# Trepanat_Output.net
KiCad netlist of a schematic drawn in Altium Designer
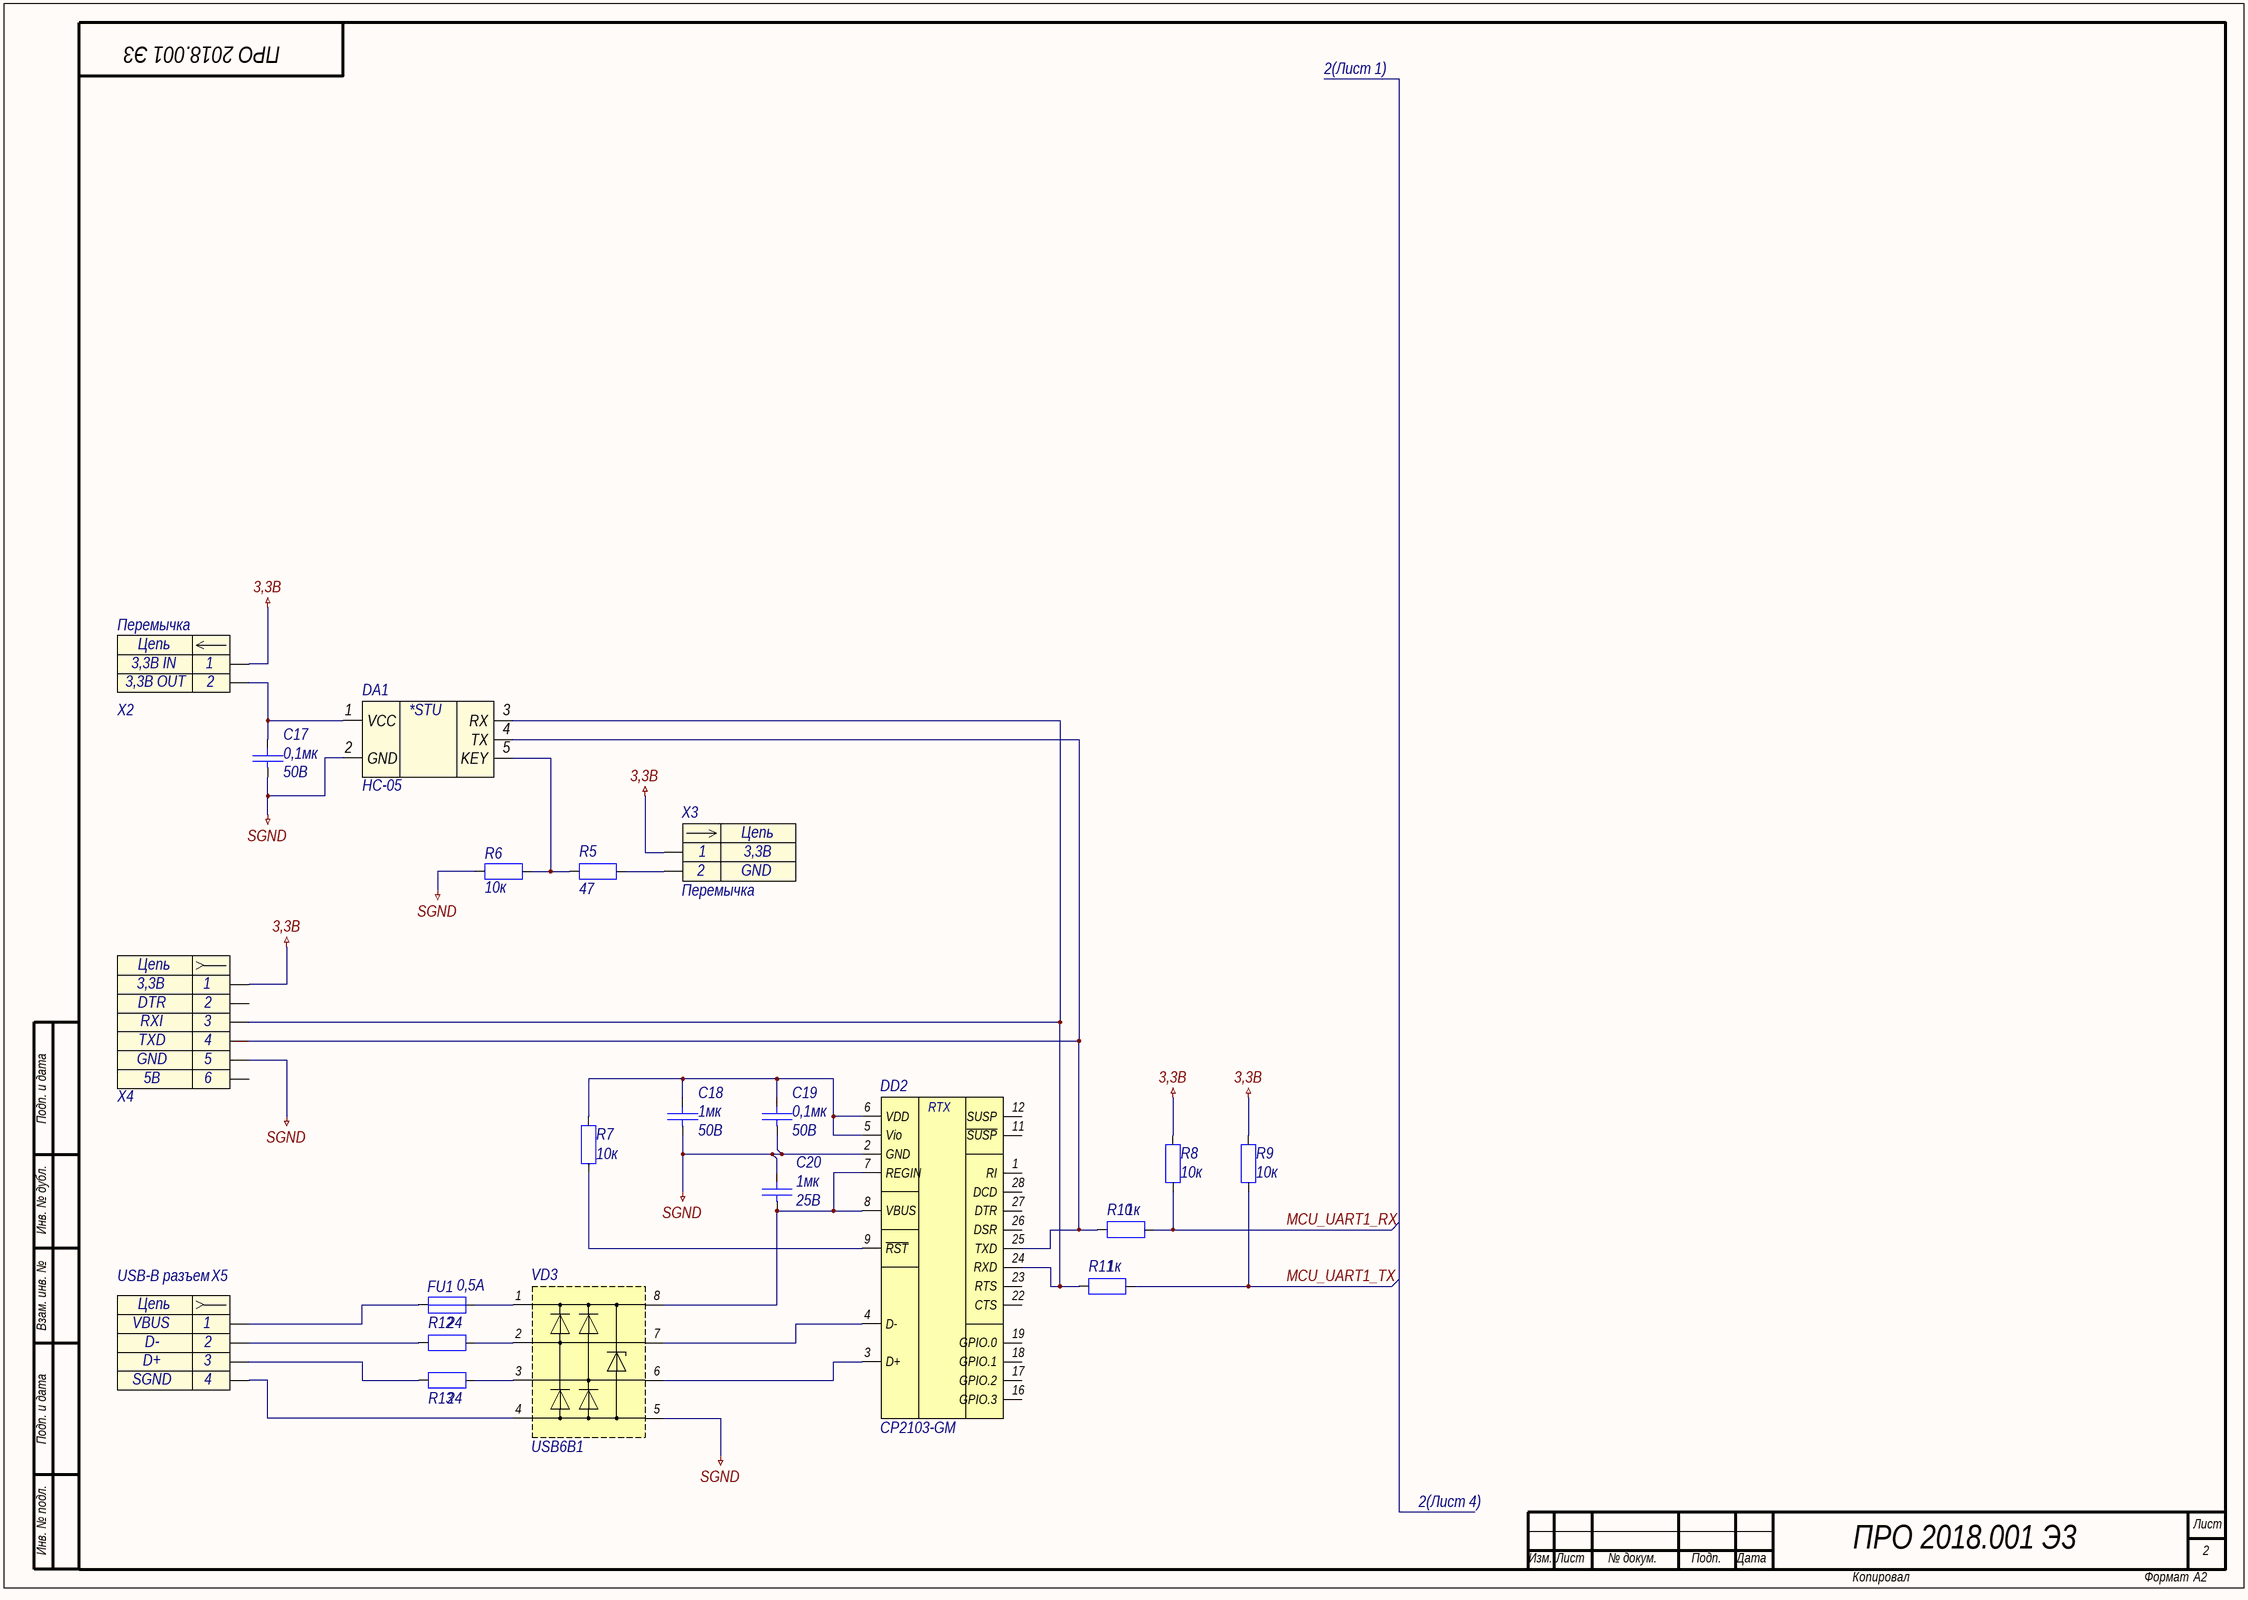
[diagram p0: Trepanat_Output.SchDoc]

(export (version "E")
  (design (tool "Eeschema 10.0.6"))
  (components
    (comp (ref "C17")
      (value "0,1мк")
      (footprint "ZabugorLib:C0805")
      (description "Конденсатор")
      (fields (field (name "VOLTAGE") "50В"))
      (libsource (lib "ZabugorLib") (part "Capacitor"))
    )
    (comp (ref "C18")
      (value "1мк")
      (footprint "ZabugorLib:C0805")
      (description "Конденсатор")
      (fields (field (name "VOLTAGE") "50В"))
      (libsource (lib "ZabugorLib") (part "Capacitor"))
    )
    (comp (ref "C19")
      (value "0,1мк")
      (footprint "ZabugorLib:C0805")
      (description "Конденсатор")
      (fields (field (name "VOLTAGE") "50В"))
      (libsource (lib "ZabugorLib") (part "Capacitor"))
    )
    (comp (ref "C20")
      (value "1мк")
      (footprint "ZabugorLib:C0805")
      (description "Конденсатор")
      (fields (field (name "VOLTAGE") "25В"))
      (libsource (lib "ZabugorLib") (part "Capacitor"))
    )
    (comp (ref "DA1")
      (value "HC-05")
      (footprint "HC-05")
      (description "Bluetooth HC-05")
      (libsource (lib "ZabugorLib") (part "HC-05"))
    )
    (comp (ref "DD2")
      (value "CP2103-GM")
      (footprint "ZabugorLib:QFN28")
      (description "USB-UART преобразователь")
      (fields (field (name "NAME") "CP2103-GM"))
      (libsource (lib "ZabugorLib") (part "CP2103"))
    )
    (comp (ref "FU1")
      (value "0,5A")
      (footprint "ZabugorLib:R1812")
      (description "Предохранитель")
      (fields (field (name "Comment") "MF-MSMF050"))
      (libsource (lib "ZabugorLib") (part "Fuse"))
    )
    (comp (ref "R5")
      (value "47")
      (footprint "ZabugorLib:R0805")
      (description "Резистор")
      (libsource (lib "") (part "Resistor_2"))
    )
    (comp (ref "R6")
      (value "10к")
      (footprint "ZabugorLib:R0805")
      (description "Резистор")
      (libsource (lib "") (part "Resistor_1"))
    )
    (comp (ref "R7")
      (value "10к")
      (footprint "ZabugorLib:R0805")
      (description "Резистор")
      (libsource (lib "ZabugorLib") (part "Resistor"))
    )
    (comp (ref "R8")
      (value "10к")
      (footprint "ZabugorLib:R0805")
      (description "Резистор")
      (libsource (lib "ZabugorLib") (part "Resistor"))
    )
    (comp (ref "R9")
      (value "10к")
      (footprint "ZabugorLib:R0805")
      (description "Резистор")
      (libsource (lib "ZabugorLib") (part "Resistor"))
    )
    (comp (ref "R10")
      (value "1к")
      (footprint "ZabugorLib:R0805")
      (description "Резистор")
      (libsource (lib "") (part "Resistor_2"))
    )
    (comp (ref "R11")
      (value "1к")
      (footprint "ZabugorLib:R0805")
      (description "Резистор")
      (libsource (lib "") (part "Resistor_2"))
    )
    (comp (ref "R12")
      (value "24")
      (footprint "ZabugorLib:R0805")
      (description "Резистор")
      (libsource (lib "") (part "Resistor_1"))
    )
    (comp (ref "R13")
      (value "24")
      (footprint "ZabugorLib:R0805")
      (description "Резистор")
      (libsource (lib "") (part "Resistor_1"))
    )
    (comp (ref "VD3")
      (value "USB6B1")
      (footprint "ZabugorLib:SO8")
      (description "Защита линии данных")
      (fields (field (name "NAME") "USB6B1"))
      (libsource (lib "ZabugorLib") (part "USB6B1"))
    )
    (comp (ref "X2")
      (value "Перемычка")
      (footprint "ZabugorLib:PLS2-2")
      (description "Разъем - 2 конт. вилка")
      (fields (field (name "NAME") "Перемычка"))
      (libsource (lib "ZabugorLib") (part "Header_2_plg"))
    )
    (comp (ref "X3")
      (value "Перемычка")
      (footprint "ZabugorLib:PLS2-2")
      (description "Разъем - 2 конт. вилка")
      (fields (field (name "NAME") "Перемычка"))
      (libsource (lib "") (part "Header_2_plg_1"))
    )
    (comp (ref "X4")
      (value "~")
      (footprint "ZabugorLib:PLS-6")
      (description "Разъем - 5 конт. розетка")
      (libsource (lib "ZabugorLib") (part "Header_6_sct"))
    )
    (comp (ref "X5")
      (value "670687041")
      (footprint "ZabugorLib:USBB-J1")
      (description "Разъем - 4 конт. розетка")
      (libsource (lib "ZabugorLib") (part "Header_4_sct"))
    )
  )
  (nets
    (net (code "1") (name "/MCU_UART1_RX") (class "Default")
      (node (ref "R10") (pin "1") (pinfunction "1_1") (pintype "passive"))
      (node (ref "R8") (pin "2") (pinfunction "2_2") (pintype "passive"))
    )
    (net (code "2") (name "/MCU_UART1_TX") (class "Default")
      (node (ref "R11") (pin "1") (pinfunction "1_1") (pintype "passive"))
      (node (ref "R9") (pin "2") (pinfunction "2_2") (pintype "passive"))
    )
    (net (code "3") (name "3,3B") (class "Default")
      (node (ref "R8") (pin "1") (pinfunction "1_1") (pintype "passive"))
      (node (ref "R9") (pin "1") (pinfunction "1_1") (pintype "passive"))
      (node (ref "X2") (pin "1") (pinfunction "1_1") (pintype "passive"))
      (node (ref "X3") (pin "1") (pinfunction "1_1") (pintype "passive"))
      (node (ref "X4") (pin "1") (pinfunction "1_1") (pintype "passive"))
    )
    (net (code "4") (name "Net-(DA1-KEY)") (class "Default")
      (node (ref "DA1") (pin "5") (pinfunction "KEY_5") (pintype "power_in"))
      (node (ref "R5") (pin "2") (pinfunction "2_2") (pintype "passive"))
      (node (ref "R6") (pin "2") (pinfunction "2_2") (pintype "passive"))
    )
    (net (code "5") (name "Net-(DA1-RX)") (class "Default")
      (node (ref "DA1") (pin "3") (pinfunction "RX_3") (pintype "power_in"))
      (node (ref "DD2") (pin "24") (pinfunction "RXD_24") (pintype "passive"))
      (node (ref "R11") (pin "2") (pinfunction "2_2") (pintype "passive"))
      (node (ref "X4") (pin "3") (pinfunction "3_3") (pintype "passive"))
    )
    (net (code "6") (name "Net-(DA1-TX)") (class "Default")
      (node (ref "DA1") (pin "4") (pinfunction "TX_4") (pintype "power_in"))
      (node (ref "DD2") (pin "25") (pinfunction "TXD_25") (pintype "passive"))
      (node (ref "R10") (pin "2") (pinfunction "2_2") (pintype "passive"))
      (node (ref "X4") (pin "4") (pinfunction "4_4") (pintype "passive"))
    )
    (net (code "7") (name "Net-(DA1-VCC)") (class "Default")
      (node (ref "C17") (pin "2") (pinfunction "2_2") (pintype "passive"))
      (node (ref "DA1") (pin "1") (pinfunction "VCC_1") (pintype "power_in"))
      (node (ref "X2") (pin "2") (pinfunction "2_2") (pintype "passive"))
    )
    (net (code "8") (name "Net-(DD2-D+)") (class "Default")
      (node (ref "DD2") (pin "3") (pinfunction "D+_3") (pintype "passive"))
      (node (ref "VD3") (pin "6") (pintype "passive"))
    )
    (net (code "9") (name "Net-(DD2-D-)") (class "Default")
      (node (ref "DD2") (pin "4") (pinfunction "D-_4") (pintype "passive"))
      (node (ref "VD3") (pin "7") (pintype "passive"))
    )
    (net (code "10") (name "Net-(DD2-REGIN)") (class "Default")
      (node (ref "C20") (pin "1") (pinfunction "1_1") (pintype "passive"))
      (node (ref "DD2") (pin "7") (pinfunction "REGIN_7") (pintype "passive"))
      (node (ref "DD2") (pin "8") (pinfunction "VBUS_8") (pintype "passive"))
      (node (ref "VD3") (pin "8") (pintype "passive"))
    )
    (net (code "11") (name "Net-(DD2-VDD)") (class "Default")
      (node (ref "C18") (pin "2") (pinfunction "2_2") (pintype "passive"))
      (node (ref "C19") (pin "2") (pinfunction "2_2") (pintype "passive"))
      (node (ref "DD2") (pin "5") (pinfunction "Vio_5") (pintype "passive"))
      (node (ref "DD2") (pin "6") (pinfunction "VDD_6") (pintype "passive"))
      (node (ref "R7") (pin "1") (pinfunction "1_1") (pintype "passive"))
    )
    (net (code "12") (name "Net-(DD2-~{RST})") (class "Default")
      (node (ref "DD2") (pin "9") (pinfunction "~{RST}_9") (pintype "passive"))
      (node (ref "R7") (pin "2") (pinfunction "2_2") (pintype "passive"))
    )
    (net (code "13") (name "Net-(FU1-Pad1)") (class "Default")
      (node (ref "FU1") (pin "1") (pinfunction "1_1") (pintype "passive"))
      (node (ref "X5") (pin "1") (pinfunction "1_1") (pintype "passive"))
    )
    (net (code "14") (name "Net-(FU1-Pad2)") (class "Default")
      (node (ref "FU1") (pin "2") (pinfunction "2_2") (pintype "passive"))
      (node (ref "VD3") (pin "1") (pintype "passive"))
    )
    (net (code "15") (name "Net-(R5-Pad1)") (class "Default")
      (node (ref "R5") (pin "1") (pinfunction "1_1") (pintype "passive"))
      (node (ref "X3") (pin "2") (pinfunction "2_2") (pintype "passive"))
    )
    (net (code "16") (name "Net-(R12-Pad1)") (class "Default")
      (node (ref "R12") (pin "1") (pinfunction "1_1") (pintype "passive"))
      (node (ref "X5") (pin "2") (pinfunction "2_2") (pintype "passive"))
    )
    (net (code "17") (name "Net-(R12-Pad2)") (class "Default")
      (node (ref "R12") (pin "2") (pinfunction "2_2") (pintype "passive"))
      (node (ref "VD3") (pin "2") (pintype "passive"))
    )
    (net (code "18") (name "Net-(R13-Pad1)") (class "Default")
      (node (ref "R13") (pin "1") (pinfunction "1_1") (pintype "passive"))
      (node (ref "X5") (pin "3") (pinfunction "3_3") (pintype "passive"))
    )
    (net (code "19") (name "Net-(R13-Pad2)") (class "Default")
      (node (ref "R13") (pin "2") (pinfunction "2_2") (pintype "passive"))
      (node (ref "VD3") (pin "3") (pintype "passive"))
    )
    (net (code "20") (name "Net-(VD3-Pad4)") (class "Default")
      (node (ref "VD3") (pin "4") (pintype "passive"))
      (node (ref "X5") (pin "4") (pinfunction "4_4") (pintype "passive"))
    )
    (net (code "21") (name "SGND") (class "Default")
      (node (ref "C17") (pin "1") (pinfunction "1_1") (pintype "passive"))
      (node (ref "C18") (pin "1") (pinfunction "1_1") (pintype "passive"))
      (node (ref "C19") (pin "1") (pinfunction "1_1") (pintype "passive"))
      (node (ref "C20") (pin "2") (pinfunction "2_2") (pintype "passive"))
      (node (ref "DA1") (pin "2") (pinfunction "GND_2") (pintype "power_in"))
      (node (ref "DD2") (pin "2") (pinfunction "GND_2") (pintype "passive"))
      (node (ref "R6") (pin "1") (pinfunction "1_1") (pintype "passive"))
      (node (ref "VD3") (pin "5") (pintype "passive"))
      (node (ref "X4") (pin "5") (pinfunction "5_5") (pintype "passive"))
    )
    (net (code "22") (name "unconnected-(DD2-CTS-Pad22)") (class "Default")
      (node (ref "DD2") (pin "22") (pinfunction "CTS_22") (pintype "passive"))
    )
    (net (code "23") (name "unconnected-(DD2-DCD-Pad28)") (class "Default")
      (node (ref "DD2") (pin "28") (pinfunction "DCD_28") (pintype "passive"))
    )
    (net (code "24") (name "unconnected-(DD2-DSR-Pad26)") (class "Default")
      (node (ref "DD2") (pin "26") (pinfunction "DSR_26") (pintype "passive"))
    )
    (net (code "25") (name "unconnected-(DD2-DTR-Pad27)") (class "Default")
      (node (ref "DD2") (pin "27") (pinfunction "DTR_27") (pintype "passive"))
    )
    (net (code "26") (name "unconnected-(DD2-GPIO.0-Pad19)") (class "Default")
      (node (ref "DD2") (pin "19") (pinfunction "GPIO.0_19") (pintype "passive"))
    )
    (net (code "27") (name "unconnected-(DD2-GPIO.1-Pad18)") (class "Default")
      (node (ref "DD2") (pin "18") (pinfunction "GPIO.1_18") (pintype "passive"))
    )
    (net (code "28") (name "unconnected-(DD2-GPIO.2-Pad17)") (class "Default")
      (node (ref "DD2") (pin "17") (pinfunction "GPIO.2_17") (pintype "passive"))
    )
    (net (code "29") (name "unconnected-(DD2-GPIO.3-Pad16)") (class "Default")
      (node (ref "DD2") (pin "16") (pinfunction "GPIO.3_16") (pintype "passive"))
    )
    (net (code "30") (name "unconnected-(DD2-RI-Pad1)") (class "Default")
      (node (ref "DD2") (pin "1") (pinfunction "RI_1") (pintype "passive"))
    )
    (net (code "31") (name "unconnected-(DD2-RTS-Pad23)") (class "Default")
      (node (ref "DD2") (pin "23") (pinfunction "RTS_23") (pintype "passive"))
    )
    (net (code "32") (name "unconnected-(DD2-SUSP-Pad12)") (class "Default")
      (node (ref "DD2") (pin "12") (pinfunction "SUSP_12") (pintype "passive"))
    )
    (net (code "33") (name "unconnected-(DD2-~{SUSP}-Pad11)") (class "Default")
      (node (ref "DD2") (pin "11") (pinfunction "~{SUSP}_11") (pintype "passive"))
    )
    (net (code "34") (name "unconnected-(X4-Pad2)") (class "Default")
      (node (ref "X4") (pin "2") (pinfunction "2_2") (pintype "passive"))
    )
    (net (code "35") (name "unconnected-(X4-Pad6)") (class "Default")
      (node (ref "X4") (pin "6") (pinfunction "6_6") (pintype "passive"))
    )
  )
)
